# indicator_light.net
KiCad netlist of a schematic drawn in Altium Designer
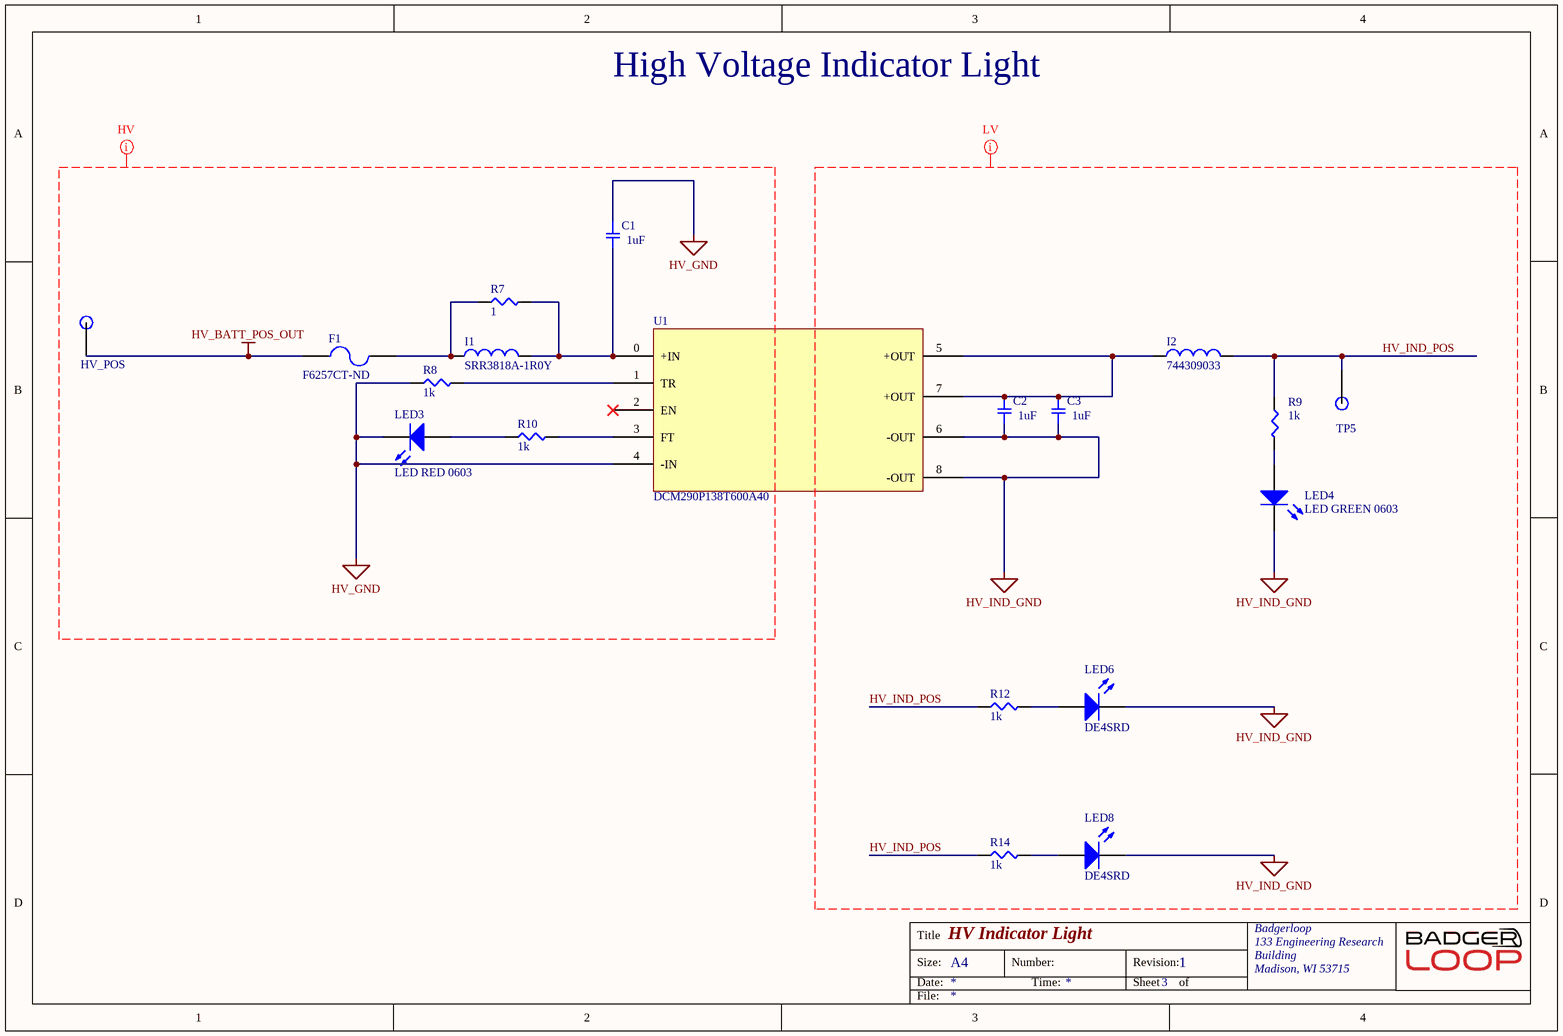
[diagram p0: indicator_light.SchDoc]

(export (version "E")
  (design (tool "Eeschema 10.0.6"))
  (components
    (comp (ref "C1")
      (value "CGA9P4X7T2W105K250KE_1")
      (footprint "CAPC5860X28N")
      (description "CAP CER 1UF 450V X7T 2220")
      (fields
        (field (name "MANUFACTURER") "TDK")
        (field (name "MANUFACTURER PART NUMBER") "CGA9P4X7T2W105K250KE")
        (field (name "CAPACITANCE") "1uF")
      )
      (libsource (lib "altium-import") (part "root_0_CGA9P4X7T2W105K250KE_1_"))
    )
    (comp (ref "C2")
      (value "CGA9P4X7T2W105K250KE_1")
      (footprint "CAPC5860X28N")
      (description "CAP CER 1UF 450V X7T 2220")
      (fields
        (field (name "MANUFACTURER") "TDK")
        (field (name "MANUFACTURER PART NUMBER") "CGA9P4X7T2W105K250KE")
        (field (name "CAPACITANCE") "1uF")
      )
      (libsource (lib "altium-import") (part "root_0_CGA9P4X7T2W105K250KE_1_"))
    )
    (comp (ref "C3")
      (value "CGA9P4X7T2W105K250KE_1")
      (footprint "CAPC5860X28N")
      (description "CAP CER 1UF 450V X7T 2220")
      (fields
        (field (name "MANUFACTURER") "TDK")
        (field (name "MANUFACTURER PART NUMBER") "CGA9P4X7T2W105K250KE")
        (field (name "CAPACITANCE") "1uF")
      )
      (libsource (lib "altium-import") (part "root_0_CGA9P4X7T2W105K250KE_1_"))
    )
    (comp (ref "F1")
      (value "F6257CT-ND")
      (footprint "SMD-0805-RES")
      (description "FUSE BOARD MNT 500MA 350VAC/VDC")
      (fields (field (name "MANUFACTURER") "Littelfuse"))
      (libsource (lib "misc") (part "F6257CT-ND"))
    )
    (comp (ref "HV_POS")
      (value "TP")
      (footprint "Test Point")
      (description "SMD TEST POINT")
      (libsource (lib "misc") (part "TP"))
    )
    (comp (ref "I1")
      (value "SRR3818A-1R0Y")
      (footprint "INDM3838X18N")
      (description "FIXED IND 1UH 3.6A 37 MOHM SMD")
      (fields (field (name "MANUFACTURER") "Bourns Inc."))
      (libsource (lib "misc") (part "SRR3818A-1R0Y"))
    )
    (comp (ref "I2")
      (value "744309033")
      (footprint "INDM140130X90N")
      (description "FIXED IND 330NH 47.5A 0.165 MOHM")
      (fields (field (name "MANUFACTURER") "Wurth"))
      (libsource (lib "misc") (part "744309033"))
    )
    (comp (ref "LED3")
      (value "LED RED 0603")
      (footprint "LED 0603 RED")
      (description "Red 631nm LED Indication - Discrete 2V 0603 (1608 Metric)")
      (fields (field (name "MANUFACTURER") "Lite-On Inc."))
      (libsource (lib "misc") (part "LED RED 0603"))
    )
    (comp (ref "LED4")
      (value "LED GREEN 0603")
      (footprint "LED 0603 GREEN")
      (fields (field (name "MANUFACTURER") "Lite-On Inc."))
      (libsource (lib "misc") (part "LED GREEN 0603"))
    )
    (comp (ref "LED6")
      (value "DE4SRD")
      (footprint "DE4SRD")
      (description "LED Bars and Arrays Red 640nm 300mcd Diffused Light Bar")
      (fields (field (name "MANUFACTURER") "Kingbright"))
      (libsource (lib "shelby_temp") (part "DE4SRD"))
    )
    (comp (ref "LED8")
      (value "DE4SRD")
      (footprint "DE4SRD")
      (description "LED Bars and Arrays Red 640nm 300mcd Diffused Light Bar")
      (fields (field (name "MANUFACTURER") "Kingbright"))
      (libsource (lib "shelby_temp") (part "DE4SRD"))
    )
    (comp (ref "R7")
      (value "1")
      (footprint "SMD-0805-RES")
      (description "RES SMD 1 OHM 5% 1/3W 0805")
      (fields (field (name "PART NUMBER") "ERJ-6BQJ1R0V") (field (name "DIGI-KEY PART NUMBER") "P17527CT-ND"))
      (libsource (lib "resistors") (part "ERJ-6BQJ1R0V"))
    )
    (comp (ref "R8")
      (value "1k")
      (footprint "SMD-0805-RES")
      (description "RES SMD 1K OHM 1% 1/8W 0805")
      (fields
        (field (name "PART NUMBER") "ERJ-6ENF1001V")
        (field (name "DIGI-KEY PART NUMBER") "P1.00KCCT-ND")
      )
      (libsource (lib "resistors") (part "ERJ-6ENF1001V"))
    )
    (comp (ref "R9")
      (value "1k")
      (footprint "SMD-0805-RES")
      (description "RES SMD 1K OHM 1% 1/8W 0805")
      (fields
        (field (name "PART NUMBER") "ERJ-6ENF1001V")
        (field (name "DIGI-KEY PART NUMBER") "P1.00KCCT-ND")
      )
      (libsource (lib "resistors") (part "ERJ-6ENF1001V"))
    )
    (comp (ref "R10")
      (value "1k")
      (footprint "SMD-0805-RES")
      (description "RES SMD 1K OHM 1% 1/8W 0805")
      (fields
        (field (name "PART NUMBER") "ERJ-6ENF1001V")
        (field (name "DIGI-KEY PART NUMBER") "P1.00KCCT-ND")
      )
      (libsource (lib "resistors") (part "ERJ-6ENF1001V"))
    )
    (comp (ref "R12")
      (value "1k")
      (footprint "SMD-0805-RES")
      (description "RES SMD 1K OHM 1% 1/8W 0805")
      (fields
        (field (name "PART NUMBER") "ERJ-6ENF1001V")
        (field (name "DIGI-KEY PART NUMBER") "P1.00KCCT-ND")
      )
      (libsource (lib "resistors") (part "ERJ-6ENF1001V"))
    )
    (comp (ref "R14")
      (value "1k")
      (footprint "SMD-0805-RES")
      (description "RES SMD 1K OHM 1% 1/8W 0805")
      (fields
        (field (name "PART NUMBER") "ERJ-6ENF1001V")
        (field (name "DIGI-KEY PART NUMBER") "P1.00KCCT-ND")
      )
      (libsource (lib "resistors") (part "ERJ-6ENF1001V"))
    )
    (comp (ref "TP5")
      (value "TP")
      (footprint "Test Point")
      (description "SMD TEST POINT")
      (libsource (lib "misc") (part "TP"))
    )
    (comp (ref "U1")
      (value "DCM290P138T600A40")
      (footprint "DCM290y138x600A40")
      (description "DC DC CONVERTER 13.8V 600W")
      (fields (field (name "MANUFACTURER") "Vicor"))
      (libsource (lib "ic") (part "DCM290P138T600A40"))
    )
  )
  (nets
    (net (code "1") (name "/HV_IND_POS") (class "Default")
      (node (ref "I2") (pin "2") (pinfunction "2_2") (pintype "passive"))
      (node (ref "R12") (pin "1") (pinfunction "1_1") (pintype "passive"))
      (node (ref "R14") (pin "1") (pinfunction "1_1") (pintype "passive"))
      (node (ref "R9") (pin "1") (pinfunction "1_1") (pintype "passive"))
      (node (ref "TP5") (pin "1") (pinfunction "1_1") (pintype "passive"))
    )
    (net (code "2") (name "HV_BATT_POS_OUT") (class "Default")
      (node (ref "F1") (pin "1") (pinfunction "1_1") (pintype "passive"))
      (node (ref "HV_POS") (pin "1") (pinfunction "1_1") (pintype "passive"))
    )
    (net (code "3") (name "HV_GND") (class "Default")
      (node (ref "C1") (pin "1") (pinfunction "1_1") (pintype "passive"))
      (node (ref "LED3") (pin "2") (pinfunction "K_2") (pintype "passive"))
      (node (ref "R8") (pin "1") (pinfunction "1_1") (pintype "passive"))
      (node (ref "U1") (pin "4") (pinfunction "-IN_4") (pintype "passive"))
    )
    (net (code "4") (name "HV_IND_GND") (class "Default")
      (node (ref "C2") (pin "2") (pinfunction "2_2") (pintype "passive"))
      (node (ref "C3") (pin "2") (pinfunction "2_2") (pintype "passive"))
      (node (ref "LED4") (pin "2") (pinfunction "K_2") (pintype "passive"))
      (node (ref "LED6") (pin "2") (pinfunction "K_2") (pintype "passive"))
      (node (ref "LED8") (pin "2") (pinfunction "K_2") (pintype "passive"))
      (node (ref "U1") (pin "6") (pinfunction "-OUT_6") (pintype "passive"))
      (node (ref "U1") (pin "8") (pinfunction "-OUT_8") (pintype "passive"))
    )
    (net (code "5") (name "Net-(C2-Pad1)") (class "Default")
      (node (ref "C2") (pin "1") (pinfunction "1_1") (pintype "passive"))
      (node (ref "C3") (pin "1") (pinfunction "1_1") (pintype "passive"))
      (node (ref "I2") (pin "1") (pinfunction "1_1") (pintype "passive"))
      (node (ref "U1") (pin "5") (pinfunction "+OUT_5") (pintype "passive"))
      (node (ref "U1") (pin "7") (pinfunction "+OUT_7") (pintype "passive"))
    )
    (net (code "6") (name "Net-(F1-Pad2)") (class "Default")
      (node (ref "F1") (pin "2") (pinfunction "2_2") (pintype "passive"))
      (node (ref "I1") (pin "1") (pinfunction "1_1") (pintype "passive"))
      (node (ref "R7") (pin "1") (pinfunction "1_1") (pintype "passive"))
    )
    (net (code "7") (name "Net-(LED3-A)") (class "Default")
      (node (ref "LED3") (pin "1") (pinfunction "A_1") (pintype "passive"))
      (node (ref "R10") (pin "1") (pinfunction "1_1") (pintype "passive"))
    )
    (net (code "8") (name "Net-(LED4-A)") (class "Default")
      (node (ref "LED4") (pin "1") (pinfunction "A_1") (pintype "passive"))
      (node (ref "R9") (pin "2") (pinfunction "2_2") (pintype "passive"))
    )
    (net (code "9") (name "Net-(LED6-A)") (class "Default")
      (node (ref "LED6") (pin "1") (pinfunction "A_1") (pintype "passive"))
      (node (ref "R12") (pin "2") (pinfunction "2_2") (pintype "passive"))
    )
    (net (code "10") (name "Net-(LED8-A)") (class "Default")
      (node (ref "LED8") (pin "1") (pinfunction "A_1") (pintype "passive"))
      (node (ref "R14") (pin "2") (pinfunction "2_2") (pintype "passive"))
    )
    (net (code "11") (name "Net-(U1-+IN)") (class "Default")
      (node (ref "C1") (pin "2") (pinfunction "2_2") (pintype "passive"))
      (node (ref "I1") (pin "2") (pinfunction "2_2") (pintype "passive"))
      (node (ref "R7") (pin "2") (pinfunction "2_2") (pintype "passive"))
      (node (ref "U1") (pin "0") (pinfunction "+IN_0") (pintype "passive"))
    )
    (net (code "12") (name "Net-(U1-FT)") (class "Default")
      (node (ref "R10") (pin "2") (pinfunction "2_2") (pintype "passive"))
      (node (ref "U1") (pin "3") (pinfunction "FT_3") (pintype "passive"))
    )
    (net (code "13") (name "Net-(U1-TR)") (class "Default")
      (node (ref "R8") (pin "2") (pinfunction "2_2") (pintype "passive"))
      (node (ref "U1") (pin "1") (pinfunction "TR_1") (pintype "passive"))
    )
    (net (code "14") (name "unconnected-(U1-EN-Pad2)") (class "Default")
      (node (ref "U1") (pin "2") (pinfunction "EN_2") (pintype "passive+no_connect"))
    )
  )
)
